# 1DD-17-mk-1_1.net
KiCad netlist of a schematic drawn in EAGLE
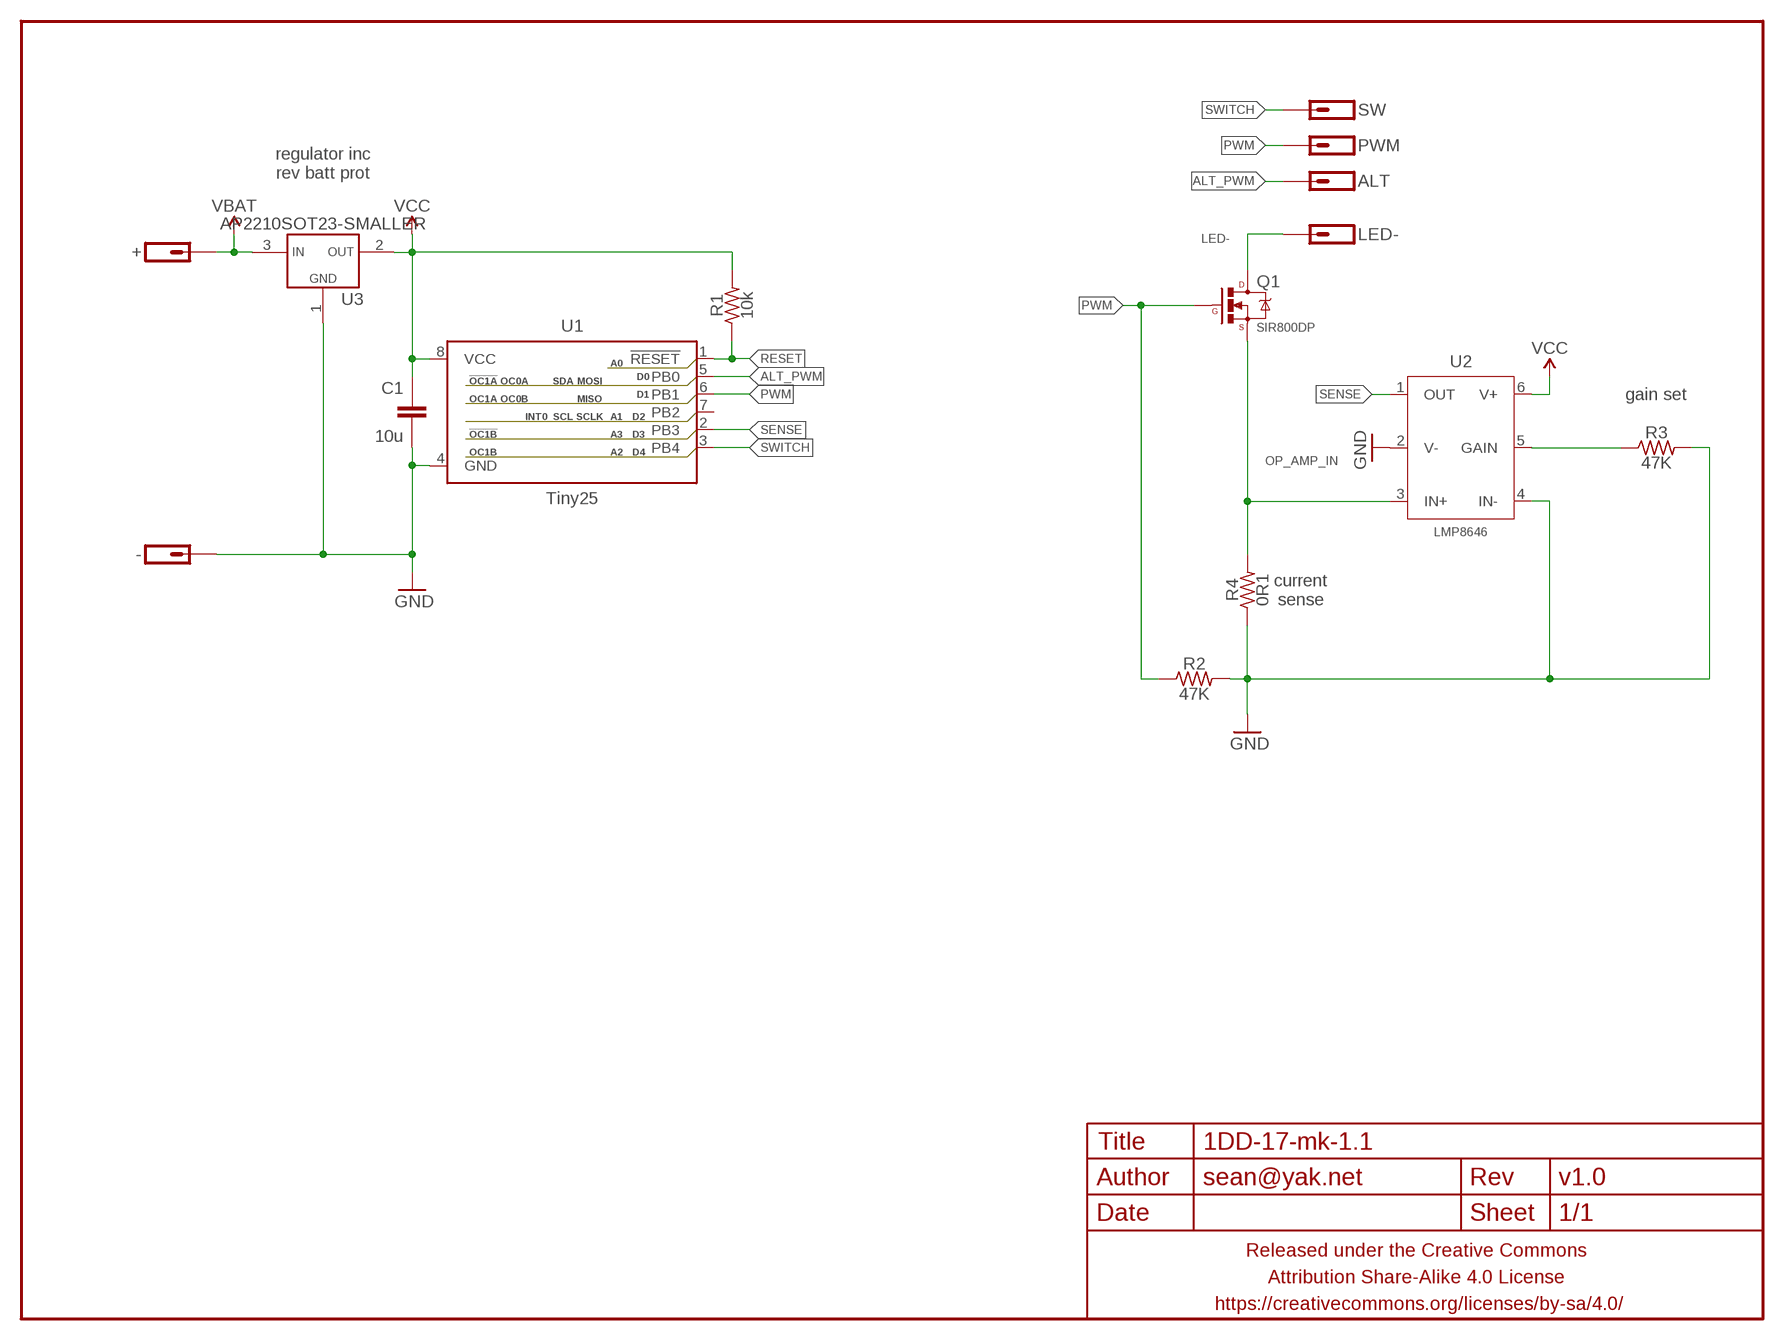
[diagram p0: schematic, sheet 1]

(export (version "E")
  (design (tool "Eeschema 10.0.6"))
  (components
    (comp (ref "+")
      (value "M01PTH-1MM-CIR-NS")
      (footprint "eagle-import:1X01-1MM-CIR-NS")
      (libsource (lib "eagle-import") (part "M01PTH-1MM-CIR-NS"))
    )
    (comp (ref "-")
      (value "M01NOT-A-VIA-NOPE")
      (footprint "eagle-import:1X01_NOSILK_NOSTOP")
      (libsource (lib "eagle-import") (part "M01NOT-A-VIA-NOPE"))
    )
    (comp (ref "ALT")
      (value "M01SMD-1MM-DIA-NS")
      (footprint "eagle-import:1X01-SMD-1MM-DIA-NS")
      (libsource (lib "eagle-import") (part "M01SMD-1MM-DIA-NS"))
    )
    (comp (ref "C1")
      (value "10u")
      (footprint "eagle-import:C0603-TIGHTER")
      (libsource (lib "eagle-import") (part "CAPACITOR-CERAMICC0603-TIGHTER"))
    )
    (comp (ref "FRAME1")
      (value "FRAME-LETTERNO_PACKAGE")
      (footprint "eagle-import:DUMMY")
      (fields (field (name "DESIGNER") "sean@yak.net") (field (name "VERSION") "v1.0"))
      (libsource (lib "eagle-import") (part "FRAME-LETTERNO_PACKAGE"))
    )
    (comp (ref "LED-")
      (value "M011X01-0.9MM-CIR")
      (footprint "eagle-import:1X01-0.9MM-CIR")
      (libsource (lib "eagle-import") (part "M011X01-0.9MM-CIR"))
    )
    (comp (ref "PWM")
      (value "M01SMD-1MM-DIA-NS")
      (footprint "eagle-import:1X01-SMD-1MM-DIA-NS")
      (libsource (lib "eagle-import") (part "M01SMD-1MM-DIA-NS"))
    )
    (comp (ref "Q1")
      (value "SIR800DP")
      (footprint "eagle-import:POWERPACK-SO-8")
      (libsource (lib "eagle-import") (part "MOSFET-NCHANNELSIR800DP"))
    )
    (comp (ref "R1")
      (value "10k")
      (footprint "eagle-import:R0402")
      (libsource (lib "eagle-import") (part "RESISTORR0402"))
    )
    (comp (ref "R2")
      (value "47K")
      (footprint "eagle-import:R0402")
      (libsource (lib "eagle-import") (part "RESISTORR0402"))
    )
    (comp (ref "R3")
      (value "47K")
      (footprint "eagle-import:R0402")
      (libsource (lib "eagle-import") (part "RESISTORR0402"))
    )
    (comp (ref "R4")
      (value "0R1")
      (footprint "eagle-import:R1206")
      (libsource (lib "eagle-import") (part "RESISTORR1206"))
    )
    (comp (ref "SW")
      (value "M01SMD-1MM-DIA-NS")
      (footprint "eagle-import:1X01-SMD-1MM-DIA-NS")
      (libsource (lib "eagle-import") (part "M01SMD-1MM-DIA-NS"))
    )
    (comp (ref "U1")
      (value "Tiny25")
      (footprint "eagle-import:SO08-NARROWER")
      (libsource (lib "eagle-import") (part "ATTINY13SOIC-NARROWPADS"))
    )
    (comp (ref "U2")
      (value "LMP8646")
      (footprint "eagle-import:SOT23-6")
      (libsource (lib "eagle-import") (part "LMP8646DDC"))
    )
    (comp (ref "U3")
      (value "AP2210SOT23-SMALLER")
      (footprint "eagle-import:SOT23-3")
      (libsource (lib "eagle-import") (part "AP2210SOT23-SMALLER"))
    )
  )
  (nets
    (net (code "1") (name "/LED-") (class "Default")
      (node (ref "LED-") (pin "P$1") (pinfunction "1_P$1") (pintype "passive"))
      (node (ref "Q1") (pin "5678") (pinfunction "D_5678") (pintype "passive"))
    )
    (net (code "2") (name "/OP_AMP_IN") (class "Default")
      (node (ref "Q1") (pin "1") (pinfunction "S_1") (pintype "passive"))
      (node (ref "Q1") (pin "2") (pinfunction "S_2") (pintype "passive"))
      (node (ref "Q1") (pin "3") (pinfunction "S_3") (pintype "passive"))
      (node (ref "R4") (pin "2") (pinfunction "2_2") (pintype "passive"))
      (node (ref "U2") (pin "3") (pinfunction "IN+_3") (pintype "bidirectional"))
    )
    (net (code "3") (name "ALT_PWM") (class "Default")
      (node (ref "ALT") (pin "P$1") (pinfunction "1_P$1") (pintype "passive"))
      (node (ref "U1") (pin "5") (pinfunction "PB0_5") (pintype "bidirectional"))
    )
    (net (code "4") (name "GND") (class "Default")
      (node (ref "-") (pin "P$1") (pinfunction "1_P$1") (pintype "passive"))
      (node (ref "C1") (pin "2") (pinfunction "2_2") (pintype "passive"))
      (node (ref "R2") (pin "2") (pinfunction "2_2") (pintype "passive"))
      (node (ref "R3") (pin "2") (pinfunction "2_2") (pintype "passive"))
      (node (ref "R4") (pin "1") (pinfunction "1_1") (pintype "passive"))
      (node (ref "U1") (pin "4") (pinfunction "GND_4") (pintype "bidirectional"))
      (node (ref "U2") (pin "2") (pinfunction "V-_2") (pintype "bidirectional"))
      (node (ref "U2") (pin "4") (pinfunction "IN-_4") (pintype "bidirectional"))
      (node (ref "U3") (pin "1") (pinfunction "GND_1") (pintype "bidirectional"))
    )
    (net (code "5") (name "Net-(U2-GAIN)") (class "Default")
      (node (ref "R3") (pin "1") (pinfunction "1_1") (pintype "passive"))
      (node (ref "U2") (pin "5") (pinfunction "GAIN_5") (pintype "bidirectional"))
    )
    (net (code "6") (name "PWM") (class "Default")
      (node (ref "PWM") (pin "P$1") (pinfunction "1_P$1") (pintype "passive"))
      (node (ref "Q1") (pin "4") (pinfunction "G_4") (pintype "passive"))
      (node (ref "R2") (pin "1") (pinfunction "1_1") (pintype "passive"))
      (node (ref "U1") (pin "6") (pinfunction "PB1_6") (pintype "bidirectional"))
    )
    (net (code "7") (name "RESET") (class "Default")
      (node (ref "R1") (pin "1") (pinfunction "1_1") (pintype "passive"))
      (node (ref "U1") (pin "1") (pinfunction "~{RESET}_1") (pintype "bidirectional"))
    )
    (net (code "8") (name "SENSE") (class "Default")
      (node (ref "U1") (pin "2") (pinfunction "PB3_2") (pintype "bidirectional"))
      (node (ref "U2") (pin "1") (pinfunction "OUT_1") (pintype "bidirectional"))
    )
    (net (code "9") (name "SWITCH") (class "Default")
      (node (ref "SW") (pin "P$1") (pinfunction "1_P$1") (pintype "passive"))
      (node (ref "U1") (pin "3") (pinfunction "PB4_3") (pintype "bidirectional"))
    )
    (net (code "10") (name "VBAT") (class "Default")
      (node (ref "+") (pin "1") (pinfunction "1_1") (pintype "passive"))
      (node (ref "U3") (pin "3") (pinfunction "VIN_3") (pintype "bidirectional"))
    )
    (net (code "11") (name "VCC") (class "Default")
      (node (ref "C1") (pin "1") (pinfunction "1_1") (pintype "passive"))
      (node (ref "R1") (pin "2") (pinfunction "2_2") (pintype "passive"))
      (node (ref "U1") (pin "8") (pinfunction "VCC_8") (pintype "bidirectional"))
      (node (ref "U2") (pin "6") (pinfunction "V+_6") (pintype "bidirectional"))
      (node (ref "U3") (pin "2") (pinfunction "VOUT_2") (pintype "bidirectional"))
    )
    (net (code "12") (name "unconnected-(U1-PB2-Pad7)") (class "Default")
      (node (ref "U1") (pin "7") (pinfunction "PB2_7") (pintype "bidirectional"))
    )
  )
)
